# Top.net
KiCad netlist of a schematic drawn in Altium Designer
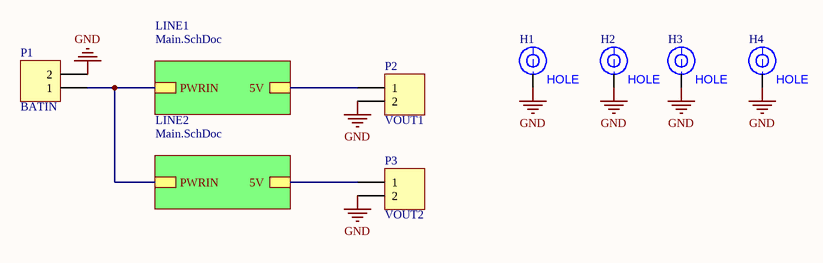
[diagram p0: Top.SchDoc]

(export (version "E")
  (design (tool "Eeschema 10.0.6"))
  (components
    (comp (ref "H1") (value "~") (footprint "铜柱-M2") (libsource (lib "我的原理图库") (part "HOLE")))
    (comp (ref "H2") (value "~") (footprint "铜柱-M2") (libsource (lib "我的原理图库") (part "HOLE")))
    (comp (ref "H3") (value "~") (footprint "铜柱-M2") (libsource (lib "我的原理图库") (part "HOLE")))
    (comp (ref "H4") (value "~") (footprint "铜柱-M2") (libsource (lib "我的原理图库") (part "HOLE")))
    (comp (ref "P1")
      (value "BATIN")
      (footprint "XT30-HF - HALF")
      (description "Header, 2-Pin")
      (fields (field (name "PUBLISHER") "Altium Limited"))
      (libsource (lib "我的原理图库") (part "Header 2"))
    )
    (comp (ref "P2")
      (value "VOUT1")
      (footprint "XT30-HF - HALF")
      (description "Header, 2-Pin")
      (fields (field (name "PUBLISHER") "Altium Limited"))
      (libsource (lib "") (part "Header 2_1"))
    )
    (comp (ref "P3")
      (value "VOUT2")
      (footprint "XT30-HF - HALF")
      (description "Header, 2-Pin")
      (fields (field (name "PUBLISHER") "Altium Limited"))
      (libsource (lib "") (part "Header 2_1"))
    )
  )
  (nets
    (net (code "1") (name "/5V") (class "Default")
      (node (ref "P3") (pin "1") (pinfunction "1_1") (pintype "passive"))
    )
    (net (code "2") (name "/5V_1") (class "Default")
      (node (ref "P2") (pin "1") (pinfunction "1_1") (pintype "passive"))
    )
    (net (code "3") (name "/PWRIN") (class "Default")
      (node (ref "P1") (pin "1") (pinfunction "1_1") (pintype "passive"))
    )
    (net (code "4") (name "GND") (class "Default")
      (node (ref "H1") (pin "0") (pinfunction "0_0") (pintype "passive"))
      (node (ref "H2") (pin "0") (pinfunction "0_0") (pintype "passive"))
      (node (ref "H3") (pin "0") (pinfunction "0_0") (pintype "passive"))
      (node (ref "H4") (pin "0") (pinfunction "0_0") (pintype "passive"))
      (node (ref "P1") (pin "2") (pinfunction "2_2") (pintype "passive"))
      (node (ref "P2") (pin "2") (pinfunction "2_2") (pintype "passive"))
      (node (ref "P3") (pin "2") (pinfunction "2_2") (pintype "passive"))
    )
  )
)
